# colourSensor.net
KiCad netlist of a schematic drawn in EAGLE
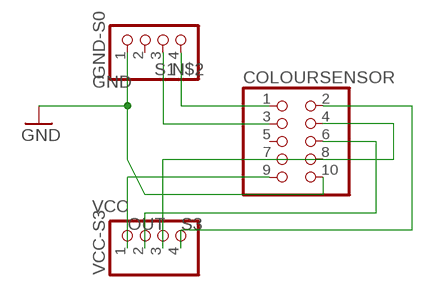
[diagram p0: schematic, sheet 1]

(export (version "E")
  (design (tool "Eeschema 10.0.6"))
  (components
    (comp (ref "COLOURSENSOR")
      (value "PINHD-2X5")
      (footprint "eagle-import:2X05")
      (libsource (lib "eagle-import") (part "PINHD-2X5"))
    )
    (comp (ref "GND-S0")
      (value "PINHD-1X4")
      (footprint "eagle-import:1X04")
      (libsource (lib "eagle-import") (part "PINHD-1X4"))
    )
    (comp (ref "VCC-S3")
      (value "PINHD-1X4")
      (footprint "eagle-import:1X04")
      (libsource (lib "eagle-import") (part "PINHD-1X4"))
    )
  )
  (nets
    (net (code "1") (name "/N$2") (class "Default")
      (node (ref "COLOURSENSOR") (pin "1") (pinfunction "1_1") (pintype "passive"))
      (node (ref "GND-S0") (pin "4") (pinfunction "4_4") (pintype "passive"))
    )
    (net (code "2") (name "/OUT") (class "Default")
      (node (ref "COLOURSENSOR") (pin "6") (pinfunction "6_6") (pintype "passive"))
      (node (ref "VCC-S3") (pin "2") (pinfunction "2_2") (pintype "passive"))
    )
    (net (code "3") (name "/S1") (class "Default")
      (node (ref "COLOURSENSOR") (pin "3") (pinfunction "3_3") (pintype "passive"))
      (node (ref "GND-S0") (pin "3") (pinfunction "3_3") (pintype "passive"))
    )
    (net (code "4") (name "/S3") (class "Default")
      (node (ref "COLOURSENSOR") (pin "2") (pinfunction "2_2") (pintype "passive"))
      (node (ref "VCC-S3") (pin "4") (pinfunction "4_4") (pintype "passive"))
    )
    (net (code "5") (name "/VCC") (class "Default")
      (node (ref "COLOURSENSOR") (pin "9") (pinfunction "9_9") (pintype "passive"))
      (node (ref "VCC-S3") (pin "1") (pinfunction "1_1") (pintype "passive"))
    )
    (net (code "6") (name "GND") (class "Default")
      (node (ref "COLOURSENSOR") (pin "10") (pinfunction "10_10") (pintype "passive"))
      (node (ref "GND-S0") (pin "1") (pinfunction "1_1") (pintype "passive"))
    )
    (net (code "7") (name "Net-(COLOURSENSOR-Pad4)") (class "Default")
      (node (ref "COLOURSENSOR") (pin "4") (pinfunction "4_4") (pintype "passive"))
      (node (ref "VCC-S3") (pin "3") (pinfunction "3_3") (pintype "passive"))
    )
    (net (code "8") (name "unconnected-(COLOURSENSOR-Pad5)") (class "Default")
      (node (ref "COLOURSENSOR") (pin "5") (pinfunction "5_5") (pintype "passive"))
    )
    (net (code "9") (name "unconnected-(COLOURSENSOR-Pad7)") (class "Default")
      (node (ref "COLOURSENSOR") (pin "7") (pinfunction "7_7") (pintype "passive"))
    )
    (net (code "10") (name "unconnected-(COLOURSENSOR-Pad8)") (class "Default")
      (node (ref "COLOURSENSOR") (pin "8") (pinfunction "8_8") (pintype "passive"))
    )
    (net (code "11") (name "unconnected-(GND-S0-Pad2)") (class "Default")
      (node (ref "GND-S0") (pin "2") (pinfunction "2_2") (pintype "passive"))
    )
  )
)
